# CBMKeyboard.net
KiCad netlist of a schematic drawn in EAGLE
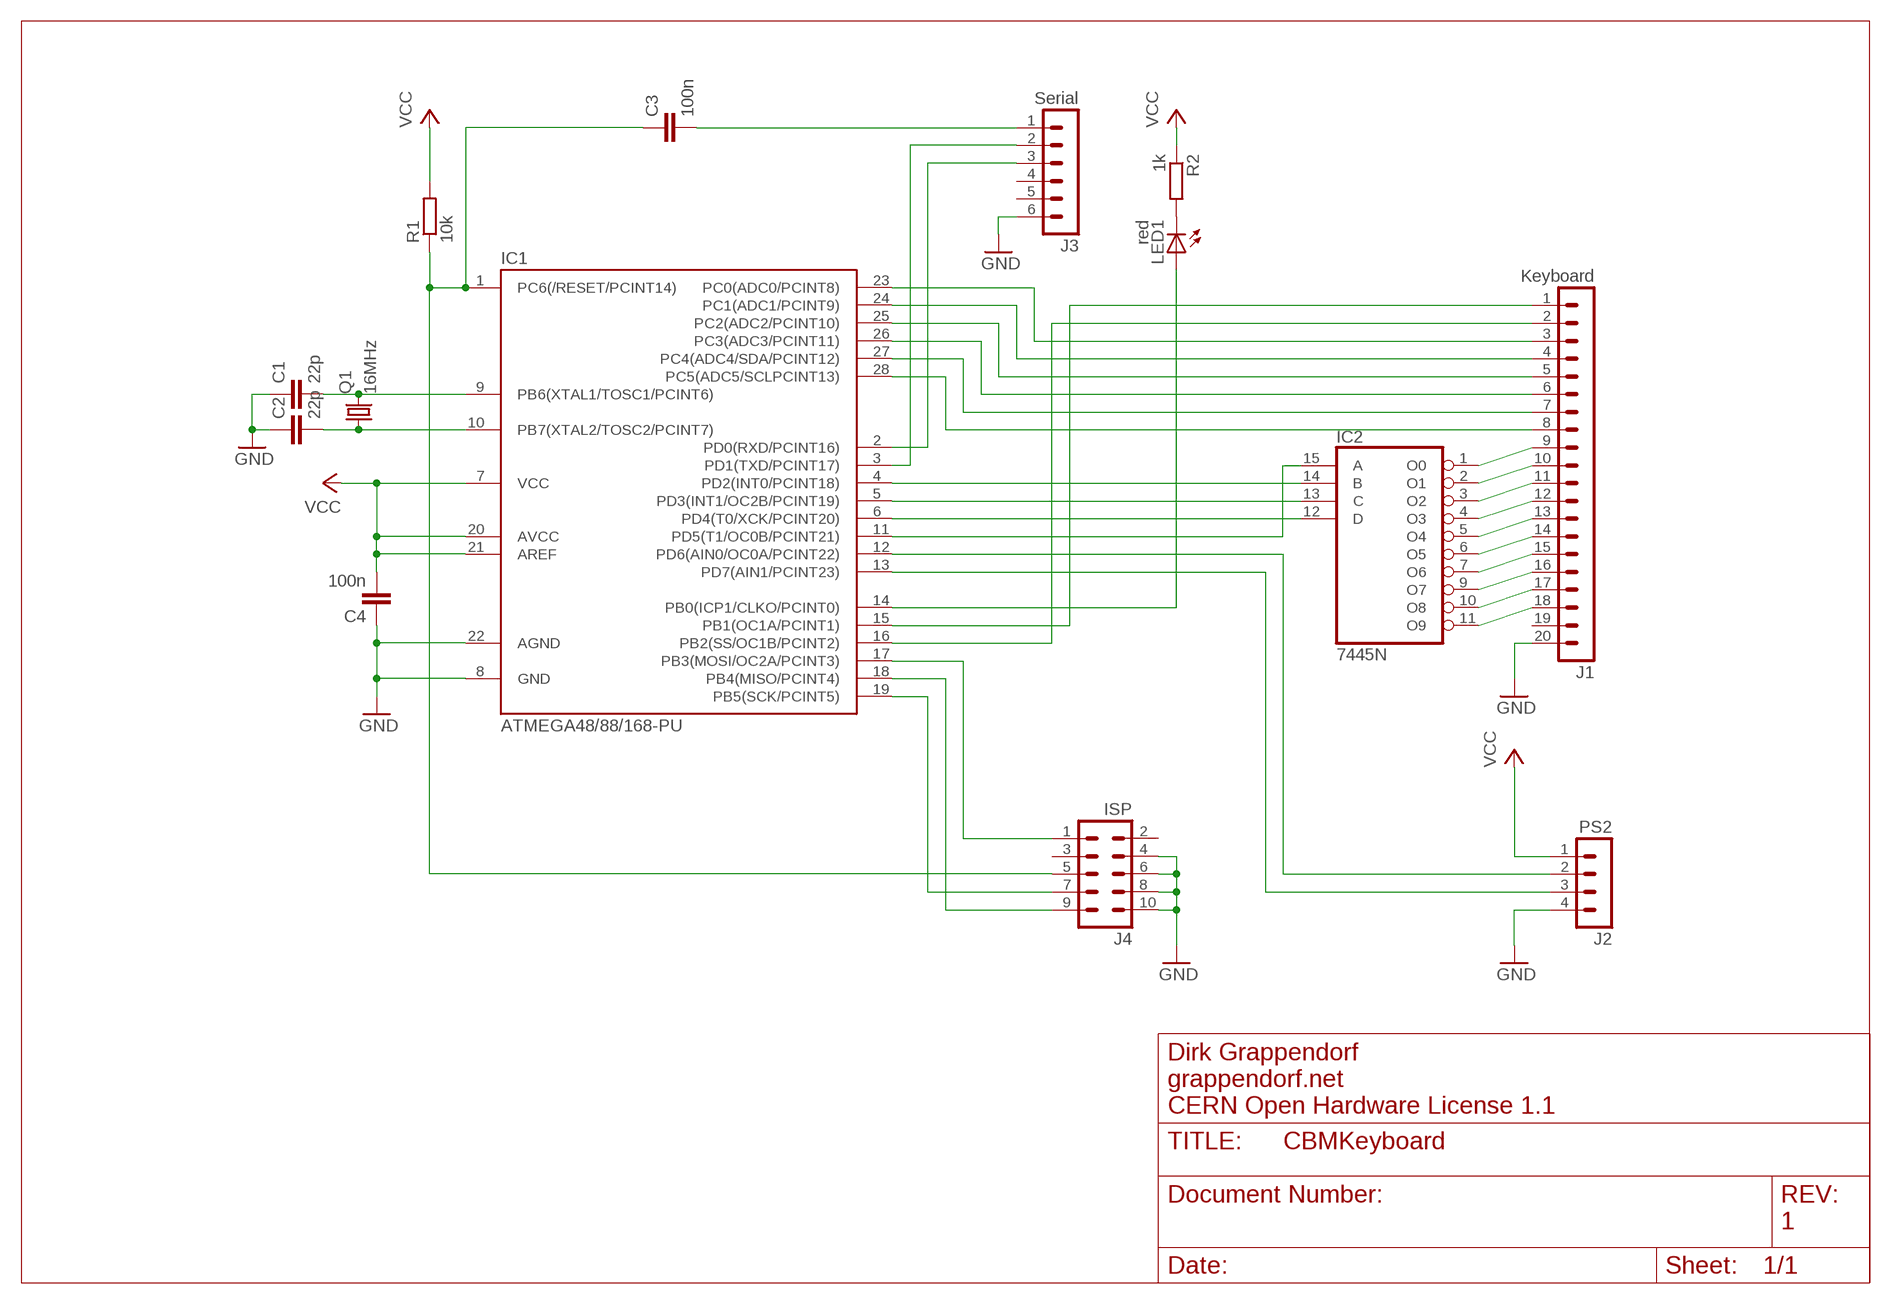
[diagram p0: schematic, sheet 1]

(export (version "E")
  (design (tool "Eeschema 10.0.6"))
  (components
    (comp (ref "C1")
      (value "22p")
      (footprint "eagle-import:C2.5-2")
      (libsource (lib "eagle-import") (part "C2.5/2"))
    )
    (comp (ref "C2")
      (value "22p")
      (footprint "eagle-import:C2.5-2")
      (libsource (lib "eagle-import") (part "C2.5/2"))
    )
    (comp (ref "C3")
      (value "100n")
      (footprint "eagle-import:C050-025X075")
      (libsource (lib "eagle-import") (part "C-EU050-025X075"))
    )
    (comp (ref "C4")
      (value "100n")
      (footprint "eagle-import:C2.5-2")
      (libsource (lib "eagle-import") (part "C2.5/2"))
    )
    (comp (ref "IC1")
      (value "ATMEGA48/88/168-PU")
      (footprint "eagle-import:DIL28-3")
      (libsource (lib "eagle-import") (part "ATMEGA48/88/168-PU"))
    )
    (comp (ref "IC2")
      (value "7445N")
      (footprint "eagle-import:DIL16")
      (libsource (lib "eagle-import") (part "7445N"))
    )
    (comp (ref "J1")
      (value "Keyboard")
      (footprint "eagle-import:MA20-1")
      (libsource (lib "eagle-import") (part "MA20-1"))
    )
    (comp (ref "J2")
      (value "PS2")
      (footprint "eagle-import:MA04-1")
      (libsource (lib "eagle-import") (part "MA04-1"))
    )
    (comp (ref "J3")
      (value "Serial")
      (footprint "eagle-import:MA06-1")
      (libsource (lib "eagle-import") (part "MA06-1"))
    )
    (comp (ref "J4")
      (value "ISP")
      (footprint "eagle-import:ML10")
      (libsource (lib "eagle-import") (part "ML10"))
    )
    (comp (ref "LED1")
      (value "red")
      (footprint "eagle-import:LED3MM")
      (libsource (lib "eagle-import") (part "LED3MM"))
    )
    (comp (ref "Q1")
      (value "16MHz")
      (footprint "eagle-import:HC49_S")
      (libsource (lib "eagle-import") (part "CRYSTALHC49S"))
    )
    (comp (ref "R1")
      (value "10k")
      (footprint "eagle-import:0207_7")
      (libsource (lib "eagle-import") (part "R-EU_0207/7"))
    )
    (comp (ref "R2")
      (value "1k")
      (footprint "eagle-import:0207_7")
      (libsource (lib "eagle-import") (part "R-EU_0207/7"))
    )
  )
  (nets
    (net (code "1") (name "GND") (class "Default")
      (node (ref "C1") (pin "1") (pinfunction "1_1") (pintype "passive"))
      (node (ref "C2") (pin "1") (pinfunction "1_1") (pintype "passive"))
      (node (ref "C4") (pin "1") (pinfunction "1_1") (pintype "passive"))
      (node (ref "IC1") (pin "22") (pinfunction "AGND_22") (pintype "power_in"))
      (node (ref "IC1") (pin "8") (pinfunction "GND_8") (pintype "power_in"))
      (node (ref "J1") (pin "20") (pinfunction "20_20") (pintype "passive"))
      (node (ref "J2") (pin "4") (pinfunction "4_4") (pintype "passive"))
      (node (ref "J3") (pin "6") (pinfunction "6_6") (pintype "passive"))
      (node (ref "J4") (pin "10") (pinfunction "10_10") (pintype "passive"))
      (node (ref "J4") (pin "4") (pinfunction "4_4") (pintype "passive"))
      (node (ref "J4") (pin "6") (pinfunction "6_6") (pintype "passive"))
      (node (ref "J4") (pin "8") (pinfunction "8_8") (pintype "passive"))
    )
    (net (code "2") (name "Net-(C3-Pad2)") (class "Default")
      (node (ref "C3") (pin "2") (pinfunction "2_2") (pintype "passive"))
      (node (ref "J3") (pin "1") (pinfunction "1_1") (pintype "passive"))
    )
    (net (code "3") (name "Net-(IC1-PB0(ICP1{slash}CLKO{slash}PCINT0))") (class "Default")
      (node (ref "IC1") (pin "14") (pinfunction "PB0(ICP1/CLKO/PCINT0)_14") (pintype "bidirectional"))
      (node (ref "LED1") (pin "A") (pinfunction "A_A") (pintype "passive"))
    )
    (net (code "4") (name "Net-(IC1-PB1(OC1A{slash}PCINT1))") (class "Default")
      (node (ref "IC1") (pin "15") (pinfunction "PB1(OC1A/PCINT1)_15") (pintype "bidirectional"))
      (node (ref "J1") (pin "1") (pinfunction "1_1") (pintype "passive"))
    )
    (net (code "5") (name "Net-(IC1-PB2(SS{slash}OC1B{slash}PCINT2))") (class "Default")
      (node (ref "IC1") (pin "16") (pinfunction "PB2(SS/OC1B/PCINT2)_16") (pintype "bidirectional"))
      (node (ref "J1") (pin "2") (pinfunction "2_2") (pintype "passive"))
    )
    (net (code "6") (name "Net-(IC1-PB3(MOSI{slash}OC2A{slash}PCINT3))") (class "Default")
      (node (ref "IC1") (pin "17") (pinfunction "PB3(MOSI/OC2A/PCINT3)_17") (pintype "bidirectional"))
      (node (ref "J4") (pin "1") (pinfunction "1_1") (pintype "passive"))
    )
    (net (code "7") (name "Net-(IC1-PB4(MISO{slash}PCINT4))") (class "Default")
      (node (ref "IC1") (pin "18") (pinfunction "PB4(MISO/PCINT4)_18") (pintype "bidirectional"))
      (node (ref "J4") (pin "9") (pinfunction "9_9") (pintype "passive"))
    )
    (net (code "8") (name "Net-(IC1-PB5(SCK{slash}PCINT5))") (class "Default")
      (node (ref "IC1") (pin "19") (pinfunction "PB5(SCK/PCINT5)_19") (pintype "bidirectional"))
      (node (ref "J4") (pin "7") (pinfunction "7_7") (pintype "passive"))
    )
    (net (code "9") (name "Net-(IC1-PB6(XTAL1{slash}TOSC1{slash}PCINT6))") (class "Default")
      (node (ref "C1") (pin "2") (pinfunction "2_2") (pintype "passive"))
      (node (ref "IC1") (pin "9") (pinfunction "PB6(XTAL1/TOSC1/PCINT6)_9") (pintype "bidirectional"))
      (node (ref "Q1") (pin "2") (pinfunction "2_2") (pintype "passive"))
    )
    (net (code "10") (name "Net-(IC1-PB7(XTAL2{slash}TOSC2{slash}PCINT7))") (class "Default")
      (node (ref "C2") (pin "2") (pinfunction "2_2") (pintype "passive"))
      (node (ref "IC1") (pin "10") (pinfunction "PB7(XTAL2/TOSC2/PCINT7)_10") (pintype "bidirectional"))
      (node (ref "Q1") (pin "1") (pinfunction "1_1") (pintype "passive"))
    )
    (net (code "11") (name "Net-(IC1-PC0(ADC0{slash}PCINT8))") (class "Default")
      (node (ref "IC1") (pin "23") (pinfunction "PC0(ADC0/PCINT8)_23") (pintype "bidirectional"))
      (node (ref "J1") (pin "3") (pinfunction "3_3") (pintype "passive"))
    )
    (net (code "12") (name "Net-(IC1-PC1(ADC1{slash}PCINT9))") (class "Default")
      (node (ref "IC1") (pin "24") (pinfunction "PC1(ADC1/PCINT9)_24") (pintype "bidirectional"))
      (node (ref "J1") (pin "4") (pinfunction "4_4") (pintype "passive"))
    )
    (net (code "13") (name "Net-(IC1-PC2(ADC2{slash}PCINT10))") (class "Default")
      (node (ref "IC1") (pin "25") (pinfunction "PC2(ADC2/PCINT10)_25") (pintype "bidirectional"))
      (node (ref "J1") (pin "5") (pinfunction "5_5") (pintype "passive"))
    )
    (net (code "14") (name "Net-(IC1-PC3(ADC3{slash}PCINT11))") (class "Default")
      (node (ref "IC1") (pin "26") (pinfunction "PC3(ADC3/PCINT11)_26") (pintype "bidirectional"))
      (node (ref "J1") (pin "6") (pinfunction "6_6") (pintype "passive"))
    )
    (net (code "15") (name "Net-(IC1-PC4(ADC4{slash}SDA{slash}PCINT12))") (class "Default")
      (node (ref "IC1") (pin "27") (pinfunction "PC4(ADC4/SDA/PCINT12)_27") (pintype "bidirectional"))
      (node (ref "J1") (pin "7") (pinfunction "7_7") (pintype "passive"))
    )
    (net (code "16") (name "Net-(IC1-PC5(ADC5{slash}SCLPCINT13))") (class "Default")
      (node (ref "IC1") (pin "28") (pinfunction "PC5(ADC5/SCLPCINT13)_28") (pintype "bidirectional"))
      (node (ref "J1") (pin "8") (pinfunction "8_8") (pintype "passive"))
    )
    (net (code "17") (name "Net-(IC1-PC6({slash}RESET{slash}PCINT14))") (class "Default")
      (node (ref "C3") (pin "1") (pinfunction "1_1") (pintype "passive"))
      (node (ref "IC1") (pin "1") (pinfunction "PC6(/RESET/PCINT14)_1") (pintype "bidirectional"))
      (node (ref "J4") (pin "5") (pinfunction "5_5") (pintype "passive"))
      (node (ref "R1") (pin "1") (pinfunction "1_1") (pintype "passive"))
    )
    (net (code "18") (name "Net-(IC1-PD0(RXD{slash}PCINT16))") (class "Default")
      (node (ref "IC1") (pin "2") (pinfunction "PD0(RXD/PCINT16)_2") (pintype "bidirectional"))
      (node (ref "J3") (pin "3") (pinfunction "3_3") (pintype "passive"))
    )
    (net (code "19") (name "Net-(IC1-PD1(TXD{slash}PCINT17))") (class "Default")
      (node (ref "IC1") (pin "3") (pinfunction "PD1(TXD/PCINT17)_3") (pintype "bidirectional"))
      (node (ref "J3") (pin "2") (pinfunction "2_2") (pintype "passive"))
    )
    (net (code "20") (name "Net-(IC1-PD2(INT0{slash}PCINT18))") (class "Default")
      (node (ref "IC1") (pin "4") (pinfunction "PD2(INT0/PCINT18)_4") (pintype "bidirectional"))
      (node (ref "IC2") (pin "14") (pinfunction "B_14") (pintype "input"))
    )
    (net (code "21") (name "Net-(IC1-PD3(INT1{slash}OC2B{slash}PCINT19))") (class "Default")
      (node (ref "IC1") (pin "5") (pinfunction "PD3(INT1/OC2B/PCINT19)_5") (pintype "bidirectional"))
      (node (ref "IC2") (pin "13") (pinfunction "C_13") (pintype "input"))
    )
    (net (code "22") (name "Net-(IC1-PD4(T0{slash}XCK{slash}PCINT20))") (class "Default")
      (node (ref "IC1") (pin "6") (pinfunction "PD4(T0/XCK/PCINT20)_6") (pintype "bidirectional"))
      (node (ref "IC2") (pin "12") (pinfunction "D_12") (pintype "input"))
    )
    (net (code "23") (name "Net-(IC1-PD5(T1{slash}OC0B{slash}PCINT21))") (class "Default")
      (node (ref "IC1") (pin "11") (pinfunction "PD5(T1/OC0B/PCINT21)_11") (pintype "bidirectional"))
      (node (ref "IC2") (pin "15") (pinfunction "A_15") (pintype "input"))
    )
    (net (code "24") (name "Net-(IC1-PD6(AIN0{slash}OC0A{slash}PCINT22))") (class "Default")
      (node (ref "IC1") (pin "12") (pinfunction "PD6(AIN0/OC0A/PCINT22)_12") (pintype "bidirectional"))
      (node (ref "J2") (pin "2") (pinfunction "2_2") (pintype "passive"))
    )
    (net (code "25") (name "Net-(IC1-PD7(AIN1{slash}PCINT23))") (class "Default")
      (node (ref "IC1") (pin "13") (pinfunction "PD7(AIN1/PCINT23)_13") (pintype "bidirectional"))
      (node (ref "J2") (pin "3") (pinfunction "3_3") (pintype "passive"))
    )
    (net (code "26") (name "Net-(IC2A-O0)") (class "Default")
      (node (ref "IC2") (pin "1") (pinfunction "O0_1") (pintype "open_collector"))
      (node (ref "J1") (pin "9") (pinfunction "9_9") (pintype "passive"))
    )
    (net (code "27") (name "Net-(IC2A-O1)") (class "Default")
      (node (ref "IC2") (pin "2") (pinfunction "O1_2") (pintype "open_collector"))
      (node (ref "J1") (pin "10") (pinfunction "10_10") (pintype "passive"))
    )
    (net (code "28") (name "Net-(IC2A-O2)") (class "Default")
      (node (ref "IC2") (pin "3") (pinfunction "O2_3") (pintype "open_collector"))
      (node (ref "J1") (pin "11") (pinfunction "11_11") (pintype "passive"))
    )
    (net (code "29") (name "Net-(IC2A-O3)") (class "Default")
      (node (ref "IC2") (pin "4") (pinfunction "O3_4") (pintype "open_collector"))
      (node (ref "J1") (pin "12") (pinfunction "12_12") (pintype "passive"))
    )
    (net (code "30") (name "Net-(IC2A-O4)") (class "Default")
      (node (ref "IC2") (pin "5") (pinfunction "O4_5") (pintype "open_collector"))
      (node (ref "J1") (pin "13") (pinfunction "13_13") (pintype "passive"))
    )
    (net (code "31") (name "Net-(IC2A-O5)") (class "Default")
      (node (ref "IC2") (pin "6") (pinfunction "O5_6") (pintype "open_collector"))
      (node (ref "J1") (pin "14") (pinfunction "14_14") (pintype "passive"))
    )
    (net (code "32") (name "Net-(IC2A-O6)") (class "Default")
      (node (ref "IC2") (pin "7") (pinfunction "O6_7") (pintype "open_collector"))
      (node (ref "J1") (pin "15") (pinfunction "15_15") (pintype "passive"))
    )
    (net (code "33") (name "Net-(IC2A-O7)") (class "Default")
      (node (ref "IC2") (pin "9") (pinfunction "O7_9") (pintype "open_collector"))
      (node (ref "J1") (pin "16") (pinfunction "16_16") (pintype "passive"))
    )
    (net (code "34") (name "Net-(IC2A-O8)") (class "Default")
      (node (ref "IC2") (pin "10") (pinfunction "O8_10") (pintype "open_collector"))
      (node (ref "J1") (pin "17") (pinfunction "17_17") (pintype "passive"))
    )
    (net (code "35") (name "Net-(IC2A-O9)") (class "Default")
      (node (ref "IC2") (pin "11") (pinfunction "O9_11") (pintype "open_collector"))
      (node (ref "J1") (pin "18") (pinfunction "18_18") (pintype "passive"))
    )
    (net (code "36") (name "Net-(LED1-C)") (class "Default")
      (node (ref "LED1") (pin "K") (pinfunction "C_K") (pintype "passive"))
      (node (ref "R2") (pin "2") (pinfunction "2_2") (pintype "passive"))
    )
    (net (code "37") (name "VCC") (class "Default")
      (node (ref "C4") (pin "2") (pinfunction "2_2") (pintype "passive"))
      (node (ref "IC1") (pin "20") (pinfunction "AVCC_20") (pintype "passive"))
      (node (ref "IC1") (pin "21") (pinfunction "AREF_21") (pintype "passive"))
      (node (ref "IC1") (pin "7") (pinfunction "VCC_7") (pintype "power_in"))
      (node (ref "J2") (pin "1") (pinfunction "1_1") (pintype "passive"))
      (node (ref "R1") (pin "2") (pinfunction "2_2") (pintype "passive"))
      (node (ref "R2") (pin "1") (pinfunction "1_1") (pintype "passive"))
    )
    (net (code "38") (name "unconnected-(J1-Pad19)") (class "Default")
      (node (ref "J1") (pin "19") (pinfunction "19_19") (pintype "passive"))
    )
    (net (code "39") (name "unconnected-(J3-Pad4)") (class "Default")
      (node (ref "J3") (pin "4") (pinfunction "4_4") (pintype "passive"))
    )
    (net (code "40") (name "unconnected-(J3-Pad5)") (class "Default")
      (node (ref "J3") (pin "5") (pinfunction "5_5") (pintype "passive"))
    )
    (net (code "41") (name "unconnected-(J4-Pad2)") (class "Default")
      (node (ref "J4") (pin "2") (pinfunction "2_2") (pintype "passive"))
    )
    (net (code "42") (name "unconnected-(J4-Pad3)") (class "Default")
      (node (ref "J4") (pin "3") (pinfunction "3_3") (pintype "passive"))
    )
  )
)
